# Smart_Relay_v2.net
KiCad netlist of a schematic drawn in EAGLE
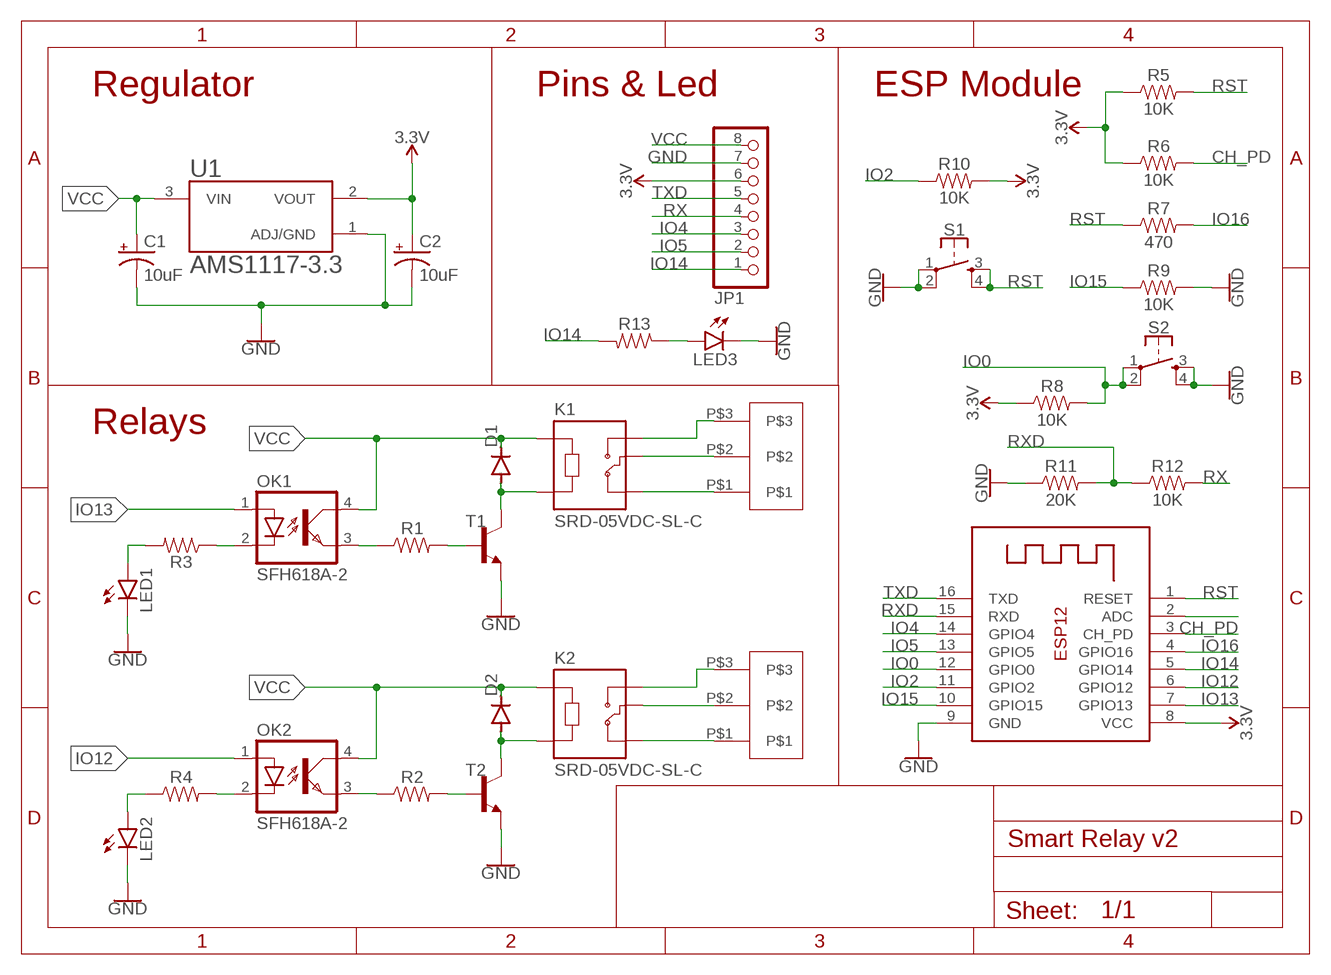
[diagram p0: schematic, sheet 1]

(export (version "E")
  (design (tool "Eeschema 10.0.6"))
  (components
    (comp (ref "C1")
      (value "10uF")
      (footprint "eagle-import:EIA3216")
      (libsource (lib "eagle-import") (part "10UF-POLAR-EIA3216-16V-10%(TANT)"))
    )
    (comp (ref "C2")
      (value "10uF")
      (footprint "eagle-import:EIA3216")
      (libsource (lib "eagle-import") (part "10UF-POLAR-EIA3216-16V-10%(TANT)"))
    )
    (comp (ref "D1")
      (value "DIODE-SOD80C")
      (footprint "eagle-import:SOD80C")
      (libsource (lib "eagle-import") (part "DIODE-SOD80C"))
    )
    (comp (ref "D2")
      (value "DIODE-SOD80C")
      (footprint "eagle-import:SOD80C")
      (libsource (lib "eagle-import") (part "DIODE-SOD80C"))
    )
    (comp (ref "JP1")
      (value "PINHD-1X8")
      (footprint "eagle-import:1X08")
      (libsource (lib "eagle-import") (part "PINHD-1X8"))
    )
    (comp (ref "K1")
      (value "SRD-05VDC-SL-C")
      (footprint "eagle-import:RELAY_SRD-05VDC-SL-C")
      (fields (field (name "MF") "Songle Relay"))
      (libsource (lib "eagle-import") (part "SRD-05VDC-SL-C"))
    )
    (comp (ref "K2")
      (value "SRD-05VDC-SL-C")
      (footprint "eagle-import:RELAY_SRD-05VDC-SL-C")
      (fields (field (name "MF") "Songle Relay"))
      (libsource (lib "eagle-import") (part "SRD-05VDC-SL-C"))
    )
    (comp (ref "LED1")
      (value "LEDCHIPLED_0805")
      (footprint "eagle-import:CHIPLED_0805")
      (libsource (lib "eagle-import") (part "LEDCHIPLED_0805"))
    )
    (comp (ref "LED2")
      (value "LEDCHIPLED_0805")
      (footprint "eagle-import:CHIPLED_0805")
      (libsource (lib "eagle-import") (part "LEDCHIPLED_0805"))
    )
    (comp (ref "LED3")
      (value "LEDCHIPLED_0805")
      (footprint "eagle-import:CHIPLED_0805")
      (libsource (lib "eagle-import") (part "LEDCHIPLED_0805"))
    )
    (comp (ref "OK1")
      (value "SFH618A-2")
      (footprint "eagle-import:DIP4")
      (fields (field (name "MF") "VISHAY/TELEFUNKEN"))
      (libsource (lib "eagle-import") (part "SFH618?A-2"))
    )
    (comp (ref "OK2")
      (value "SFH618A-2")
      (footprint "eagle-import:DIP4")
      (fields (field (name "MF") "VISHAY/TELEFUNKEN"))
      (libsource (lib "eagle-import") (part "SFH618?A-2"))
    )
    (comp (ref "R1")
      (value "RESISTOR0805")
      (footprint "eagle-import:0805")
      (libsource (lib "eagle-import") (part "RESISTOR0805"))
    )
    (comp (ref "R2")
      (value "RESISTOR0805")
      (footprint "eagle-import:0805")
      (libsource (lib "eagle-import") (part "RESISTOR0805"))
    )
    (comp (ref "R3")
      (value "RESISTOR0805")
      (footprint "eagle-import:0805")
      (libsource (lib "eagle-import") (part "RESISTOR0805"))
    )
    (comp (ref "R4")
      (value "RESISTOR0805")
      (footprint "eagle-import:0805")
      (libsource (lib "eagle-import") (part "RESISTOR0805"))
    )
    (comp (ref "R5")
      (value "10K")
      (footprint "eagle-import:0805")
      (libsource (lib "eagle-import") (part "RESISTOR0805"))
    )
    (comp (ref "R6")
      (value "10K")
      (footprint "eagle-import:0805")
      (libsource (lib "eagle-import") (part "RESISTOR0805"))
    )
    (comp (ref "R7")
      (value "470")
      (footprint "eagle-import:0805")
      (libsource (lib "eagle-import") (part "RESISTOR0805"))
    )
    (comp (ref "R8")
      (value "10K")
      (footprint "eagle-import:0805")
      (libsource (lib "eagle-import") (part "RESISTOR0805"))
    )
    (comp (ref "R9")
      (value "10K")
      (footprint "eagle-import:0805")
      (libsource (lib "eagle-import") (part "RESISTOR0805"))
    )
    (comp (ref "R10")
      (value "10K")
      (footprint "eagle-import:0805")
      (libsource (lib "eagle-import") (part "RESISTOR0805"))
    )
    (comp (ref "R11")
      (value "20K")
      (footprint "eagle-import:0805")
      (libsource (lib "eagle-import") (part "RESISTOR0805"))
    )
    (comp (ref "R12")
      (value "10K")
      (footprint "eagle-import:0805")
      (libsource (lib "eagle-import") (part "RESISTOR0805"))
    )
    (comp (ref "R13")
      (value "RESISTOR0805")
      (footprint "eagle-import:0805")
      (libsource (lib "eagle-import") (part "RESISTOR0805"))
    )
    (comp (ref "S1")
      (value "MOMENTARY-SWITCH-SPST-2-SMD-5.2MM-TALL")
      (footprint "eagle-import:TACTILE_SWITCH_SMD_5.2MM")
      (libsource (lib "eagle-import") (part "MOMENTARY-SWITCH-SPST-2-SMD-5.2MM-TALL"))
    )
    (comp (ref "S2")
      (value "MOMENTARY-SWITCH-SPST-2-SMD-5.2MM-TALL")
      (footprint "eagle-import:TACTILE_SWITCH_SMD_5.2MM")
      (libsource (lib "eagle-import") (part "MOMENTARY-SWITCH-SPST-2-SMD-5.2MM-TALL"))
    )
    (comp (ref "T1")
      (value "BC817-NPN-SOT23-BEC")
      (footprint "eagle-import:SOT23-BEC")
      (libsource (lib "eagle-import") (part "-NPN-SOT23-BECBC817"))
    )
    (comp (ref "T2")
      (value "BC817-NPN-SOT23-BEC")
      (footprint "eagle-import:SOT23-BEC")
      (libsource (lib "eagle-import") (part "-NPN-SOT23-BECBC817"))
    )
    (comp (ref "U$1")
      (value "5MM_TERMINAL_3P")
      (footprint "eagle-import:5MM_TERMINAL_3P")
      (libsource (lib "eagle-import") (part "5MM_TERMINAL_3P"))
    )
    (comp (ref "U$2")
      (value "5MM_TERMINAL_3P")
      (footprint "eagle-import:5MM_TERMINAL_3P")
      (libsource (lib "eagle-import") (part "5MM_TERMINAL_3P"))
    )
    (comp (ref "U1")
      (value "AMS1117-3.3")
      (footprint "eagle-import:SOT229P700X180-4N")
      (fields (field (name "MF") "Advanced Monolithic Systems"))
      (libsource (lib "eagle-import") (part "AMS1117-3.3"))
    )
    (comp (ref "X1")
      (value "ESP-12")
      (footprint "eagle-import:ESP-12")
      (libsource (lib "eagle-import") (part "ESP-12"))
    )
  )
  (nets
    (net (code "1") (name "/CH_PD") (class "Default")
      (node (ref "R6") (pin "2") (pinfunction "2_2") (pintype "passive"))
      (node (ref "X1") (pin "3") (pinfunction "CH_PD_3") (pintype "input"))
    )
    (net (code "2") (name "/IO0") (class "Default")
      (node (ref "R8") (pin "2") (pinfunction "2_2") (pintype "passive"))
      (node (ref "S2") (pin "1") (pinfunction "1_1") (pintype "passive"))
      (node (ref "S2") (pin "2") (pinfunction "2_2") (pintype "passive"))
      (node (ref "X1") (pin "12") (pinfunction "GPIO0_12") (pintype "bidirectional"))
    )
    (net (code "3") (name "/IO2") (class "Default")
      (node (ref "R10") (pin "1") (pinfunction "1_1") (pintype "passive"))
      (node (ref "X1") (pin "11") (pinfunction "GPIO2_11") (pintype "bidirectional"))
    )
    (net (code "4") (name "/IO4") (class "Default")
      (node (ref "JP1") (pin "3") (pinfunction "3_3") (pintype "passive"))
      (node (ref "X1") (pin "14") (pinfunction "GPIO4_14") (pintype "bidirectional"))
    )
    (net (code "5") (name "/IO5") (class "Default")
      (node (ref "JP1") (pin "2") (pinfunction "2_2") (pintype "passive"))
      (node (ref "X1") (pin "13") (pinfunction "GPIO5_13") (pintype "bidirectional"))
    )
    (net (code "6") (name "/IO14") (class "Default")
      (node (ref "JP1") (pin "1") (pinfunction "1_1") (pintype "passive"))
      (node (ref "R13") (pin "2") (pinfunction "2_2") (pintype "passive"))
      (node (ref "X1") (pin "5") (pinfunction "GPIO14_5") (pintype "bidirectional"))
    )
    (net (code "7") (name "/IO15") (class "Default")
      (node (ref "R9") (pin "1") (pinfunction "1_1") (pintype "passive"))
      (node (ref "X1") (pin "10") (pinfunction "GPIO15_10") (pintype "bidirectional"))
    )
    (net (code "8") (name "/IO16") (class "Default")
      (node (ref "R7") (pin "2") (pinfunction "2_2") (pintype "passive"))
      (node (ref "X1") (pin "4") (pinfunction "GPIO16_4") (pintype "bidirectional"))
    )
    (net (code "9") (name "/RST") (class "Default")
      (node (ref "R5") (pin "2") (pinfunction "2_2") (pintype "passive"))
      (node (ref "R7") (pin "1") (pinfunction "1_1") (pintype "passive"))
      (node (ref "S1") (pin "3") (pinfunction "3_3") (pintype "passive"))
      (node (ref "S1") (pin "4") (pinfunction "4_4") (pintype "passive"))
      (node (ref "X1") (pin "1") (pinfunction "RESET_1") (pintype "input"))
    )
    (net (code "10") (name "/RX") (class "Default")
      (node (ref "JP1") (pin "4") (pinfunction "4_4") (pintype "passive"))
      (node (ref "R12") (pin "2") (pinfunction "2_2") (pintype "passive"))
    )
    (net (code "11") (name "/RXD") (class "Default")
      (node (ref "R11") (pin "2") (pinfunction "2_2") (pintype "passive"))
      (node (ref "R12") (pin "1") (pinfunction "1_1") (pintype "passive"))
      (node (ref "X1") (pin "15") (pinfunction "RXD_15") (pintype "input"))
    )
    (net (code "12") (name "/TXD") (class "Default")
      (node (ref "JP1") (pin "5") (pinfunction "5_5") (pintype "passive"))
      (node (ref "X1") (pin "16") (pinfunction "TXD_16") (pintype "output"))
    )
    (net (code "13") (name "3.3V") (class "Default")
      (node (ref "C2") (pin "+") (pinfunction "+_+") (pintype "passive"))
      (node (ref "JP1") (pin "6") (pinfunction "6_6") (pintype "passive"))
      (node (ref "R10") (pin "2") (pinfunction "2_2") (pintype "passive"))
      (node (ref "R5") (pin "1") (pinfunction "1_1") (pintype "passive"))
      (node (ref "R6") (pin "1") (pinfunction "1_1") (pintype "passive"))
      (node (ref "R8") (pin "1") (pinfunction "1_1") (pintype "passive"))
      (node (ref "U1") (pin "2") (pinfunction "VOUT_2") (pintype "output"))
      (node (ref "X1") (pin "8") (pinfunction "VCC_8") (pintype "power_in"))
    )
    (net (code "14") (name "GND") (class "Default")
      (node (ref "C1") (pin "-") (pinfunction "-_-") (pintype "passive"))
      (node (ref "C2") (pin "-") (pinfunction "-_-") (pintype "passive"))
      (node (ref "JP1") (pin "7") (pinfunction "7_7") (pintype "passive"))
      (node (ref "LED1") (pin "C") (pinfunction "C_C") (pintype "passive"))
      (node (ref "LED2") (pin "C") (pinfunction "C_C") (pintype "passive"))
      (node (ref "LED3") (pin "C") (pinfunction "C_C") (pintype "passive"))
      (node (ref "R11") (pin "1") (pinfunction "1_1") (pintype "passive"))
      (node (ref "R9") (pin "2") (pinfunction "2_2") (pintype "passive"))
      (node (ref "S1") (pin "1") (pinfunction "1_1") (pintype "passive"))
      (node (ref "S1") (pin "2") (pinfunction "2_2") (pintype "passive"))
      (node (ref "S2") (pin "3") (pinfunction "3_3") (pintype "passive"))
      (node (ref "S2") (pin "4") (pinfunction "4_4") (pintype "passive"))
      (node (ref "T1") (pin "E") (pinfunction "E_E") (pintype "passive"))
      (node (ref "T2") (pin "E") (pinfunction "E_E") (pintype "passive"))
      (node (ref "U1") (pin "1") (pinfunction "ADJ/GND_1") (pintype "power_in"))
      (node (ref "X1") (pin "9") (pinfunction "GND_9") (pintype "power_in"))
    )
    (net (code "15") (name "IO12") (class "Default")
      (node (ref "OK2") (pin "1") (pinfunction "A_1") (pintype "passive"))
      (node (ref "X1") (pin "6") (pinfunction "GPIO12_6") (pintype "bidirectional"))
    )
    (net (code "16") (name "IO13") (class "Default")
      (node (ref "OK1") (pin "1") (pinfunction "A_1") (pintype "passive"))
      (node (ref "X1") (pin "7") (pinfunction "GPIO13_7") (pintype "bidirectional"))
    )
    (net (code "17") (name "Net-(D1-PadA)") (class "Default")
      (node (ref "D1") (pin "A") (pinfunction "A_A") (pintype "passive"))
      (node (ref "K1") (pin "A2") (pinfunction "A2_A2") (pintype "passive"))
      (node (ref "T1") (pin "C") (pinfunction "C_C") (pintype "passive"))
    )
    (net (code "18") (name "Net-(D2-PadA)") (class "Default")
      (node (ref "D2") (pin "A") (pinfunction "A_A") (pintype "passive"))
      (node (ref "K2") (pin "A2") (pinfunction "A2_A2") (pintype "passive"))
      (node (ref "T2") (pin "C") (pinfunction "C_C") (pintype "passive"))
    )
    (net (code "19") (name "Net-(K1-PadCOM)") (class "Default")
      (node (ref "K1") (pin "COM") (pinfunction "COM_COM") (pintype "passive"))
      (node (ref "U$1") (pin "P$2") (pinfunction "P$2_P$2") (pintype "bidirectional"))
    )
    (net (code "20") (name "Net-(K1-PadNC)") (class "Default")
      (node (ref "K1") (pin "NC") (pinfunction "NC_NC") (pintype "passive"))
      (node (ref "U$1") (pin "P$1") (pinfunction "P$1_P$1") (pintype "bidirectional"))
    )
    (net (code "21") (name "Net-(K1-PadNO)") (class "Default")
      (node (ref "K1") (pin "NO") (pinfunction "NO_NO") (pintype "passive"))
      (node (ref "U$1") (pin "P$3") (pinfunction "P$3_P$3") (pintype "bidirectional"))
    )
    (net (code "22") (name "Net-(K2-PadCOM)") (class "Default")
      (node (ref "K2") (pin "COM") (pinfunction "COM_COM") (pintype "passive"))
      (node (ref "U$2") (pin "P$2") (pinfunction "P$2_P$2") (pintype "bidirectional"))
    )
    (net (code "23") (name "Net-(K2-PadNC)") (class "Default")
      (node (ref "K2") (pin "NC") (pinfunction "NC_NC") (pintype "passive"))
      (node (ref "U$2") (pin "P$1") (pinfunction "P$1_P$1") (pintype "bidirectional"))
    )
    (net (code "24") (name "Net-(K2-PadNO)") (class "Default")
      (node (ref "K2") (pin "NO") (pinfunction "NO_NO") (pintype "passive"))
      (node (ref "U$2") (pin "P$3") (pinfunction "P$3_P$3") (pintype "bidirectional"))
    )
    (net (code "25") (name "Net-(LED1-PadA)") (class "Default")
      (node (ref "LED1") (pin "A") (pinfunction "A_A") (pintype "passive"))
      (node (ref "R3") (pin "2") (pinfunction "2_2") (pintype "passive"))
    )
    (net (code "26") (name "Net-(LED2-PadA)") (class "Default")
      (node (ref "LED2") (pin "A") (pinfunction "A_A") (pintype "passive"))
      (node (ref "R4") (pin "1") (pinfunction "1_1") (pintype "passive"))
    )
    (net (code "27") (name "Net-(LED3-PadA)") (class "Default")
      (node (ref "LED3") (pin "A") (pinfunction "A_A") (pintype "passive"))
      (node (ref "R13") (pin "1") (pinfunction "1_1") (pintype "passive"))
    )
    (net (code "28") (name "Net-(OK1-C)") (class "Default")
      (node (ref "OK1") (pin "2") (pinfunction "C_2") (pintype "passive"))
      (node (ref "R3") (pin "1") (pinfunction "1_1") (pintype "passive"))
    )
    (net (code "29") (name "Net-(OK1-EMIT)") (class "Default")
      (node (ref "OK1") (pin "3") (pinfunction "EMIT_3") (pintype "passive"))
      (node (ref "R1") (pin "1") (pinfunction "1_1") (pintype "passive"))
    )
    (net (code "30") (name "Net-(OK2-C)") (class "Default")
      (node (ref "OK2") (pin "2") (pinfunction "C_2") (pintype "passive"))
      (node (ref "R4") (pin "2") (pinfunction "2_2") (pintype "passive"))
    )
    (net (code "31") (name "Net-(OK2-EMIT)") (class "Default")
      (node (ref "OK2") (pin "3") (pinfunction "EMIT_3") (pintype "passive"))
      (node (ref "R2") (pin "1") (pinfunction "1_1") (pintype "passive"))
    )
    (net (code "32") (name "Net-(R1-Pad2)") (class "Default")
      (node (ref "R1") (pin "2") (pinfunction "2_2") (pintype "passive"))
      (node (ref "T1") (pin "B") (pinfunction "B_B") (pintype "passive"))
    )
    (net (code "33") (name "Net-(R2-Pad2)") (class "Default")
      (node (ref "R2") (pin "2") (pinfunction "2_2") (pintype "passive"))
      (node (ref "T2") (pin "B") (pinfunction "B_B") (pintype "passive"))
    )
    (net (code "34") (name "VCC") (class "Default")
      (node (ref "C1") (pin "+") (pinfunction "+_+") (pintype "passive"))
      (node (ref "D1") (pin "C") (pinfunction "C_C") (pintype "passive"))
      (node (ref "D2") (pin "C") (pinfunction "C_C") (pintype "passive"))
      (node (ref "JP1") (pin "8") (pinfunction "8_8") (pintype "passive"))
      (node (ref "K1") (pin "A1") (pinfunction "A1_A1") (pintype "passive"))
      (node (ref "K2") (pin "A1") (pinfunction "A1_A1") (pintype "passive"))
      (node (ref "OK1") (pin "4") (pinfunction "COL_4") (pintype "passive"))
      (node (ref "OK2") (pin "4") (pinfunction "COL_4") (pintype "passive"))
      (node (ref "U1") (pin "3") (pinfunction "VIN_3") (pintype "input"))
    )
    (net (code "35") (name "unconnected-(X1-ADC-Pad2)") (class "Default")
      (node (ref "X1") (pin "2") (pinfunction "ADC_2") (pintype "passive"))
    )
  )
)
